# ADE9000_prototipo.net
KiCad netlist of a schematic drawn in EAGLE
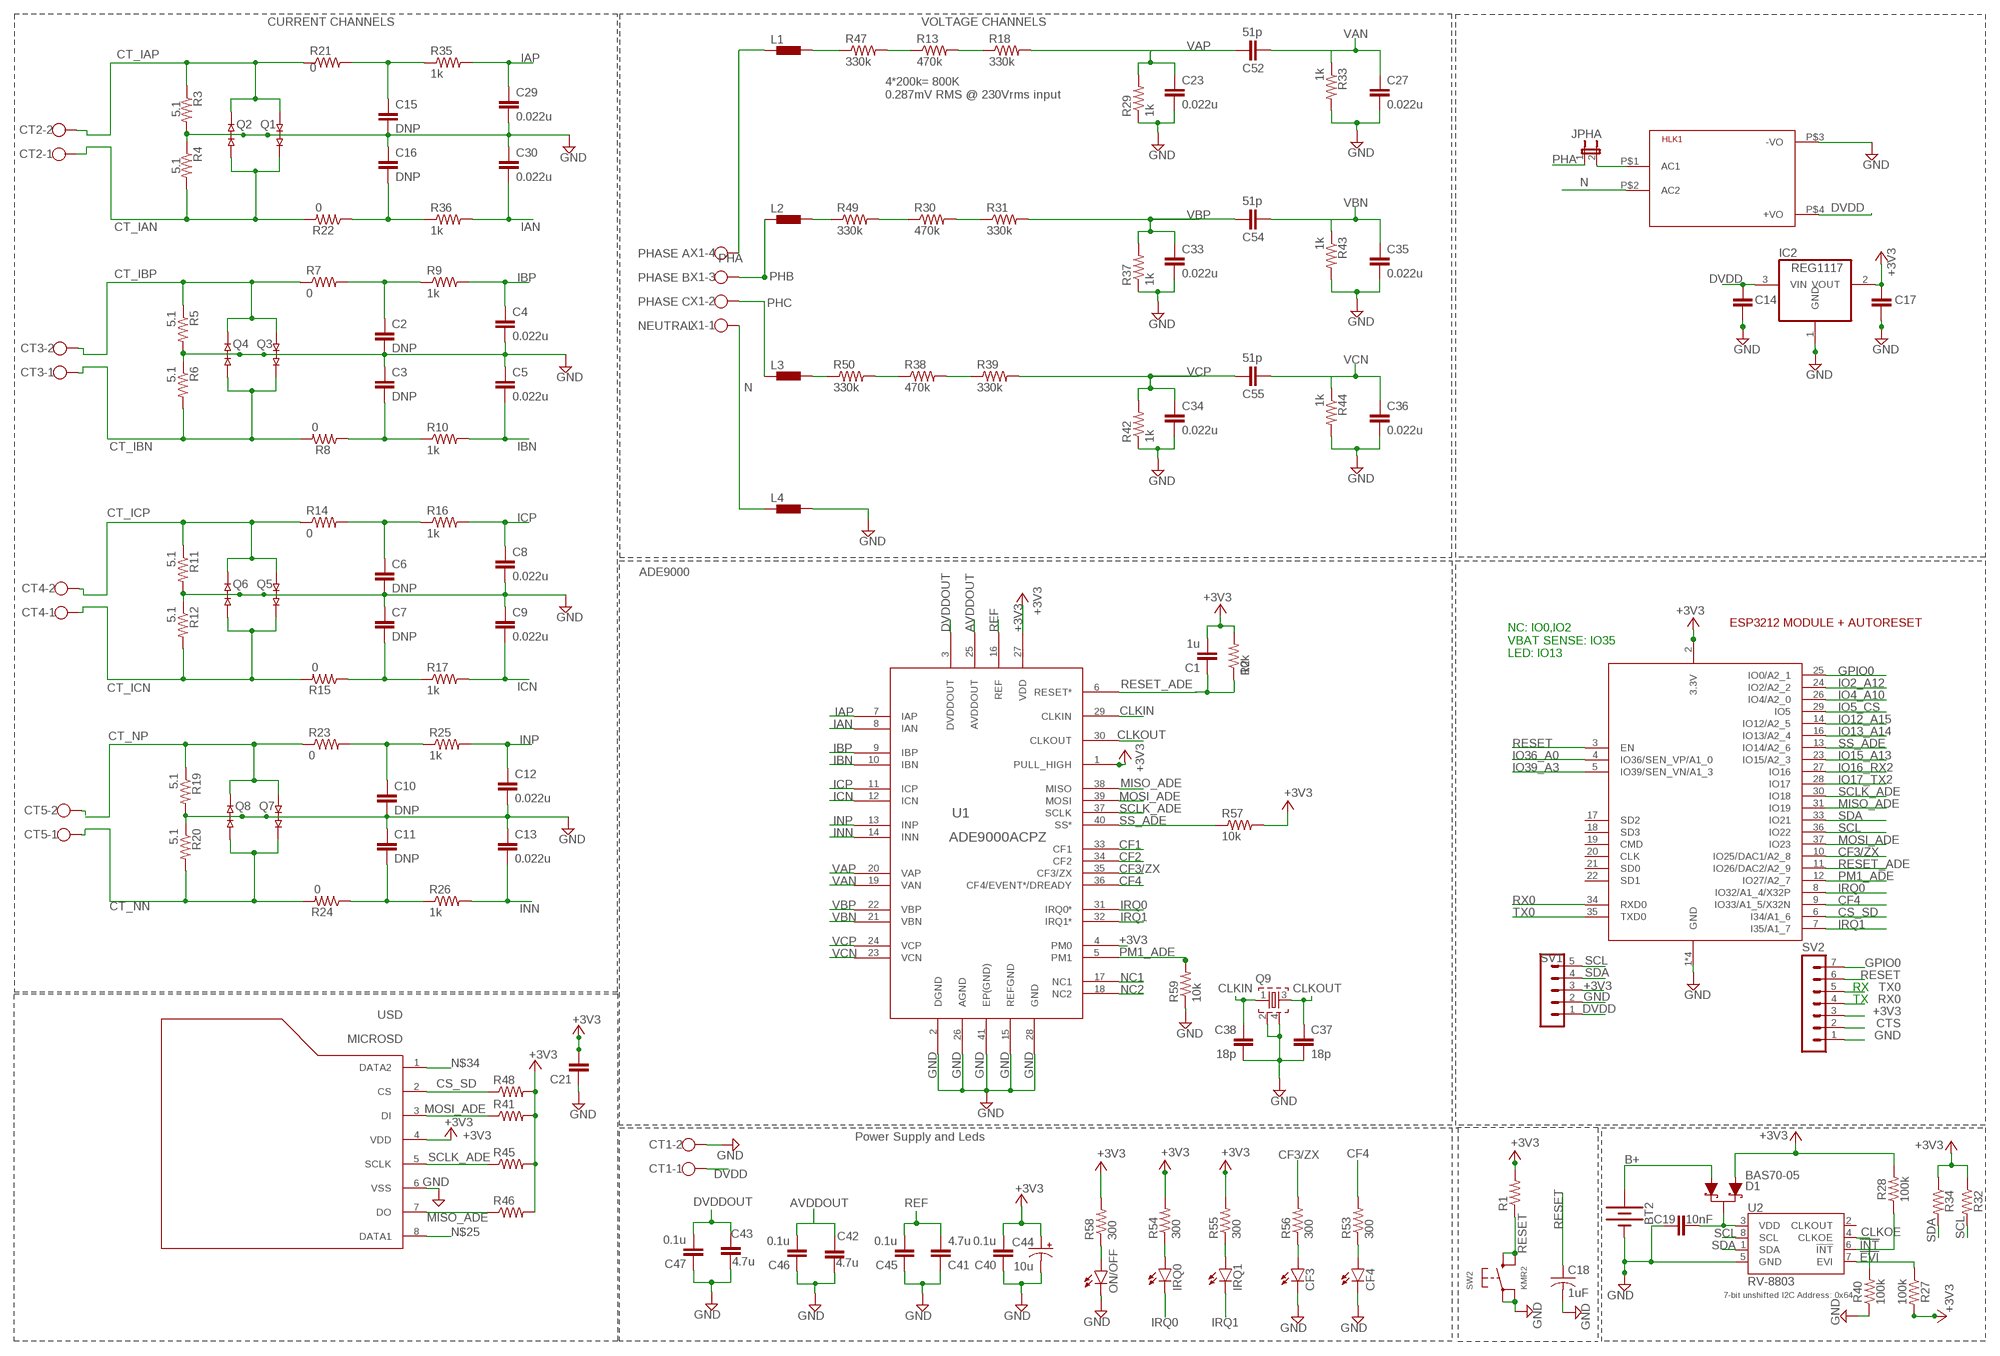
[diagram p0: schematic, sheet 1]

(export (version "E")
  (design (tool "Eeschema 10.0.6"))
  (components
    (comp (ref "BT2")
      (value "BATTERY-12MM_SMD")
      (footprint "eagle-import:BATTCON_12MM")
      (libsource (lib "eagle-import") (part "BATTERY-12MM_SMD"))
    )
    (comp (ref "C1")
      (value "1u")
      (footprint "eagle-import:C0805")
      (libsource (lib "eagle-import") (part "C-EUC0805"))
    )
    (comp (ref "C2")
      (value "DNP")
      (footprint "eagle-import:C0805")
      (libsource (lib "eagle-import") (part "C-EUC0805"))
    )
    (comp (ref "C3")
      (value "DNP")
      (footprint "eagle-import:C0805")
      (libsource (lib "eagle-import") (part "C-EUC0805"))
    )
    (comp (ref "C4")
      (value "0.022u")
      (footprint "eagle-import:C0805")
      (libsource (lib "eagle-import") (part "C-EUC0805"))
    )
    (comp (ref "C5")
      (value "0.022u")
      (footprint "eagle-import:C0805")
      (libsource (lib "eagle-import") (part "C-EUC0805"))
    )
    (comp (ref "C6")
      (value "DNP")
      (footprint "eagle-import:C0805")
      (libsource (lib "eagle-import") (part "C-EUC0805"))
    )
    (comp (ref "C7")
      (value "DNP")
      (footprint "eagle-import:C0805")
      (libsource (lib "eagle-import") (part "C-EUC0805"))
    )
    (comp (ref "C8")
      (value "0.022u")
      (footprint "eagle-import:C0805")
      (libsource (lib "eagle-import") (part "C-EUC0805"))
    )
    (comp (ref "C9")
      (value "0.022u")
      (footprint "eagle-import:C0805")
      (libsource (lib "eagle-import") (part "C-EUC0805"))
    )
    (comp (ref "C10")
      (value "DNP")
      (footprint "eagle-import:C0805")
      (libsource (lib "eagle-import") (part "C-EUC0805"))
    )
    (comp (ref "C11")
      (value "DNP")
      (footprint "eagle-import:C0805")
      (libsource (lib "eagle-import") (part "C-EUC0805"))
    )
    (comp (ref "C12")
      (value "0.022u")
      (footprint "eagle-import:C0805")
      (libsource (lib "eagle-import") (part "C-EUC0805"))
    )
    (comp (ref "C13")
      (value "0.022u")
      (footprint "eagle-import:C0805")
      (libsource (lib "eagle-import") (part "C-EUC0805"))
    )
    (comp (ref "C14")
      (value "C-EUC1206")
      (footprint "eagle-import:C1206")
      (libsource (lib "eagle-import") (part "C-EUC1206"))
    )
    (comp (ref "C15")
      (value "DNP")
      (footprint "eagle-import:C0805")
      (libsource (lib "eagle-import") (part "C-EUC0805"))
    )
    (comp (ref "C16")
      (value "DNP")
      (footprint "eagle-import:C0805")
      (libsource (lib "eagle-import") (part "C-EUC0805"))
    )
    (comp (ref "C17")
      (value "C-EUC1206")
      (footprint "eagle-import:C1206")
      (libsource (lib "eagle-import") (part "C-EUC1206"))
    )
    (comp (ref "C18")
      (value "1uF")
      (footprint "eagle-import:C0805")
      (libsource (lib "eagle-import") (part "C-USC0805"))
    )
    (comp (ref "C19")
      (value "10nF")
      (footprint "eagle-import:0603")
      (libsource (lib "eagle-import") (part "10NF-0603-50V-10%"))
    )
    (comp (ref "C21")
      (value "0.1u")
      (footprint "eagle-import:C0805")
      (libsource (lib "eagle-import") (part "C-EUC0805"))
    )
    (comp (ref "C23")
      (value "0.022u")
      (footprint "eagle-import:C0805")
      (libsource (lib "eagle-import") (part "C-EUC0805"))
    )
    (comp (ref "C27")
      (value "0.022u")
      (footprint "eagle-import:C0603")
      (libsource (lib "eagle-import") (part "C-EUC0603"))
    )
    (comp (ref "C29")
      (value "0.022u")
      (footprint "eagle-import:C0805")
      (libsource (lib "eagle-import") (part "C-EUC0805"))
    )
    (comp (ref "C30")
      (value "0.022u")
      (footprint "eagle-import:C0805")
      (libsource (lib "eagle-import") (part "C-EUC0805"))
    )
    (comp (ref "C33")
      (value "0.022u")
      (footprint "eagle-import:C0805")
      (libsource (lib "eagle-import") (part "C-EUC0805"))
    )
    (comp (ref "C34")
      (value "0.022u")
      (footprint "eagle-import:C0805")
      (libsource (lib "eagle-import") (part "C-EUC0805"))
    )
    (comp (ref "C35")
      (value "0.022u")
      (footprint "eagle-import:C0603")
      (libsource (lib "eagle-import") (part "C-EUC0603"))
    )
    (comp (ref "C36")
      (value "0.022u")
      (footprint "eagle-import:C0603")
      (libsource (lib "eagle-import") (part "C-EUC0603"))
    )
    (comp (ref "C37")
      (value "18p")
      (footprint "eagle-import:C0805")
      (libsource (lib "eagle-import") (part "C-EUC0805"))
    )
    (comp (ref "C38")
      (value "18p")
      (footprint "eagle-import:C0805")
      (libsource (lib "eagle-import") (part "C-EUC0805"))
    )
    (comp (ref "C40")
      (value "0.1u")
      (footprint "eagle-import:C0805")
      (libsource (lib "eagle-import") (part "C-EUC0805"))
    )
    (comp (ref "C41")
      (value "4.7u")
      (footprint "eagle-import:C0805")
      (libsource (lib "eagle-import") (part "C-EUC0805"))
    )
    (comp (ref "C42")
      (value "4.7u")
      (footprint "eagle-import:C0805")
      (libsource (lib "eagle-import") (part "C-EUC0805"))
    )
    (comp (ref "C43")
      (value "4.7u")
      (footprint "eagle-import:C0805")
      (libsource (lib "eagle-import") (part "C-EUC0805"))
    )
    (comp (ref "C44")
      (value "10u")
      (footprint "eagle-import:E1,8-4")
      (libsource (lib "eagle-import") (part "CPOL-USE1.8-4"))
    )
    (comp (ref "C45")
      (value "0.1u")
      (footprint "eagle-import:C0805")
      (libsource (lib "eagle-import") (part "C-EUC0805"))
    )
    (comp (ref "C46")
      (value "0.1u")
      (footprint "eagle-import:C0805")
      (libsource (lib "eagle-import") (part "C-EUC0805"))
    )
    (comp (ref "C47")
      (value "0.1u")
      (footprint "eagle-import:C0805")
      (libsource (lib "eagle-import") (part "C-EUC0805"))
    )
    (comp (ref "C52")
      (value "51p")
      (footprint "eagle-import:C0603")
      (libsource (lib "eagle-import") (part "C-EUC0603"))
    )
    (comp (ref "C54")
      (value "51p")
      (footprint "eagle-import:C0603")
      (libsource (lib "eagle-import") (part "C-EUC0603"))
    )
    (comp (ref "C55")
      (value "51p")
      (footprint "eagle-import:C0603")
      (libsource (lib "eagle-import") (part "C-EUC0603"))
    )
    (comp (ref "CF3")
      (value "LEDCHIPLED_1206")
      (footprint "eagle-import:CHIPLED_1206")
      (libsource (lib "eagle-import") (part "LEDCHIPLED_1206"))
    )
    (comp (ref "CF4")
      (value "LEDCHIPLED_1206")
      (footprint "eagle-import:CHIPLED_1206")
      (libsource (lib "eagle-import") (part "LEDCHIPLED_1206"))
    )
    (comp (ref "CT1")
      (value "W237-102")
      (footprint "eagle-import:W237-102")
      (fields (field (name "MPN") "237-102"))
      (libsource (lib "eagle-import") (part "W237-102"))
    )
    (comp (ref "CT2")
      (value "W237-102")
      (footprint "eagle-import:W237-102")
      (fields (field (name "MPN") "237-102"))
      (libsource (lib "eagle-import") (part "W237-102"))
    )
    (comp (ref "CT3")
      (value "W237-102")
      (footprint "eagle-import:W237-102")
      (fields (field (name "MPN") "237-102"))
      (libsource (lib "eagle-import") (part "W237-102"))
    )
    (comp (ref "CT4")
      (value "W237-102")
      (footprint "eagle-import:W237-102")
      (fields (field (name "MPN") "237-102"))
      (libsource (lib "eagle-import") (part "W237-102"))
    )
    (comp (ref "CT5")
      (value "W237-102")
      (footprint "eagle-import:W237-102")
      (fields (field (name "MPN") "237-102"))
      (libsource (lib "eagle-import") (part "W237-102"))
    )
    (comp (ref "D1")
      (value "BAS70-05")
      (footprint "eagle-import:SOT23-3")
      (libsource (lib "eagle-import") (part "DIODE-SCHOTTKY-DUAL"))
    )
    (comp (ref "HLK1")
      (value "HLK-PM013W")
      (footprint "eagle-import:HLK-PM01")
      (libsource (lib "eagle-import") (part "HLK-PM013W"))
    )
    (comp (ref "IC2")
      (value "REG1117")
      (footprint "eagle-import:SOT223")
      (libsource (lib "eagle-import") (part "REG1117"))
    )
    (comp (ref "IRQ0")
      (value "LEDCHIPLED_1206")
      (footprint "eagle-import:CHIPLED_1206")
      (libsource (lib "eagle-import") (part "LEDCHIPLED_1206"))
    )
    (comp (ref "IRQ1")
      (value "LEDCHIPLED_1206")
      (footprint "eagle-import:CHIPLED_1206")
      (libsource (lib "eagle-import") (part "LEDCHIPLED_1206"))
    )
    (comp (ref "JPHA")
      (value "JP1E")
      (footprint "eagle-import:JP1")
      (libsource (lib "eagle-import") (part "JP1E"))
    )
    (comp (ref "L1")
      (value "1500")
      (footprint "eagle-import:M0805")
      (libsource (lib "eagle-import") (part "FERRITE_BEAD0805"))
    )
    (comp (ref "L2")
      (value "1500")
      (footprint "eagle-import:M0805")
      (libsource (lib "eagle-import") (part "FERRITE_BEAD0805"))
    )
    (comp (ref "L3")
      (value "1500")
      (footprint "eagle-import:M0805")
      (libsource (lib "eagle-import") (part "FERRITE_BEAD0805"))
    )
    (comp (ref "L4")
      (value "1500")
      (footprint "eagle-import:M0805")
      (libsource (lib "eagle-import") (part "FERRITE_BEAD0805"))
    )
    (comp (ref "ON/OFF")
      (value "LEDCHIPLED_1206")
      (footprint "eagle-import:CHIPLED_1206")
      (libsource (lib "eagle-import") (part "LEDCHIPLED_1206"))
    )
    (comp (ref "Q1")
      (value "MMBD4148SE")
      (footprint "eagle-import:SOT23-3")
      (libsource (lib "eagle-import") (part "DUAL_DIODE_SOT23-3"))
    )
    (comp (ref "Q2")
      (value "MMBD4148SE")
      (footprint "eagle-import:SOT23-3")
      (libsource (lib "eagle-import") (part "DUAL_DIODE_SOT23-3"))
    )
    (comp (ref "Q3")
      (value "MMBD4148SE")
      (footprint "eagle-import:SOT23-3")
      (libsource (lib "eagle-import") (part "DUAL_DIODE_SOT23-3"))
    )
    (comp (ref "Q4")
      (value "MMBD4148SE")
      (footprint "eagle-import:SOT23-3")
      (libsource (lib "eagle-import") (part "DUAL_DIODE_SOT23-3"))
    )
    (comp (ref "Q5")
      (value "MMBD4148SE")
      (footprint "eagle-import:SOT23-3")
      (libsource (lib "eagle-import") (part "DUAL_DIODE_SOT23-3"))
    )
    (comp (ref "Q6")
      (value "MMBD4148SE")
      (footprint "eagle-import:SOT23-3")
      (libsource (lib "eagle-import") (part "DUAL_DIODE_SOT23-3"))
    )
    (comp (ref "Q7")
      (value "MMBD4148SE")
      (footprint "eagle-import:SOT23-3")
      (libsource (lib "eagle-import") (part "DUAL_DIODE_SOT23-3"))
    )
    (comp (ref "Q8")
      (value "MMBD4148SE")
      (footprint "eagle-import:SOT23-3")
      (libsource (lib "eagle-import") (part "DUAL_DIODE_SOT23-3"))
    )
    (comp (ref "Q9")
      (value "ECS-245.7-12-33Q-JES-TR")
      (footprint "eagle-import:SMD_4PIN_3.2X2.1")
      (libsource (lib "eagle-import") (part "CRYSTAL_SMD128"))
    )
    (comp (ref "R1")
      (value "R-US_R0805")
      (footprint "eagle-import:R0805")
      (libsource (lib "eagle-import") (part "R-US_R0805"))
    )
    (comp (ref "R2")
      (value "10k")
      (footprint "eagle-import:R0805")
      (libsource (lib "eagle-import") (part "R-US_R0805"))
    )
    (comp (ref "R3")
      (value "5.1")
      (footprint "eagle-import:R0805")
      (description "RES, 5.1, 0W1, 0%1, 0805-SMT, ROHS")
      (fields (field (name "MANUFACTURER") " TE Connectivity Passive Product"))
      (libsource (lib "eagle-import") (part "R-US_R0805"))
    )
    (comp (ref "R4")
      (value "5.1")
      (footprint "eagle-import:R0805")
      (libsource (lib "eagle-import") (part "R-US_R0805"))
    )
    (comp (ref "R5")
      (value "5.1")
      (footprint "eagle-import:R0805")
      (description "RES, 5.1, 0W1, 0%1, 0805-SMT, ROHS")
      (fields (field (name "MANUFACTURER") " TE Connectivity Passive Product"))
      (libsource (lib "eagle-import") (part "R-US_R0805"))
    )
    (comp (ref "R6")
      (value "5.1")
      (footprint "eagle-import:R0805")
      (libsource (lib "eagle-import") (part "R-US_R0805"))
    )
    (comp (ref "R7")
      (value "0")
      (footprint "eagle-import:R0805")
      (libsource (lib "eagle-import") (part "R-US_R0805"))
    )
    (comp (ref "R8")
      (value "0")
      (footprint "eagle-import:R0805")
      (libsource (lib "eagle-import") (part "R-US_R0805"))
    )
    (comp (ref "R9")
      (value "1k")
      (footprint "eagle-import:R0805")
      (libsource (lib "eagle-import") (part "R-US_R0805"))
    )
    (comp (ref "R10")
      (value "1k")
      (footprint "eagle-import:R0805")
      (libsource (lib "eagle-import") (part "R-US_R0805"))
    )
    (comp (ref "R11")
      (value "5.1")
      (footprint "eagle-import:R0805")
      (description "RES, 5.1, 0W1, 0%1, 0805-SMT, ROHS")
      (fields (field (name "MANUFACTURER") " TE Connectivity Passive Product"))
      (libsource (lib "eagle-import") (part "R-US_R0805"))
    )
    (comp (ref "R12")
      (value "5.1")
      (footprint "eagle-import:R0805")
      (libsource (lib "eagle-import") (part "R-US_R0805"))
    )
    (comp (ref "R13")
      (value "470k")
      (footprint "eagle-import:R0805")
      (libsource (lib "eagle-import") (part "R-US_R0805"))
    )
    (comp (ref "R14")
      (value "0")
      (footprint "eagle-import:R0805")
      (libsource (lib "eagle-import") (part "R-US_R0805"))
    )
    (comp (ref "R15")
      (value "0")
      (footprint "eagle-import:R0805")
      (libsource (lib "eagle-import") (part "R-US_R0805"))
    )
    (comp (ref "R16")
      (value "1k")
      (footprint "eagle-import:R0805")
      (libsource (lib "eagle-import") (part "R-US_R0805"))
    )
    (comp (ref "R17")
      (value "1k")
      (footprint "eagle-import:R0805")
      (libsource (lib "eagle-import") (part "R-US_R0805"))
    )
    (comp (ref "R18")
      (value "330k")
      (footprint "eagle-import:R0805")
      (libsource (lib "eagle-import") (part "R-US_R0805"))
    )
    (comp (ref "R19")
      (value "5.1")
      (footprint "eagle-import:R0805")
      (description "RES, 5.1, 0W1, 0%1, 0805-SMT, ROHS")
      (fields (field (name "MANUFACTURER") " TE Connectivity Passive Product"))
      (libsource (lib "eagle-import") (part "R-US_R0805"))
    )
    (comp (ref "R20")
      (value "5.1")
      (footprint "eagle-import:R0805")
      (libsource (lib "eagle-import") (part "R-US_R0805"))
    )
    (comp (ref "R21")
      (value "0")
      (footprint "eagle-import:R0805")
      (libsource (lib "eagle-import") (part "R-US_R0805"))
    )
    (comp (ref "R22")
      (value "0")
      (footprint "eagle-import:R0805")
      (libsource (lib "eagle-import") (part "R-US_R0805"))
    )
    (comp (ref "R23")
      (value "0")
      (footprint "eagle-import:R0805")
      (libsource (lib "eagle-import") (part "R-US_R0805"))
    )
    (comp (ref "R24")
      (value "0")
      (footprint "eagle-import:R0805")
      (libsource (lib "eagle-import") (part "R-US_R0805"))
    )
    (comp (ref "R25")
      (value "1k")
      (footprint "eagle-import:R0805")
      (libsource (lib "eagle-import") (part "R-US_R0805"))
    )
    (comp (ref "R26")
      (value "1k")
      (footprint "eagle-import:R0805")
      (libsource (lib "eagle-import") (part "R-US_R0805"))
    )
    (comp (ref "R27")
      (value "100k")
      (footprint "eagle-import:0603")
      (libsource (lib "eagle-import") (part "100KOHM-0603-1/10W-1%"))
    )
    (comp (ref "R28")
      (value "100k")
      (footprint "eagle-import:0603")
      (libsource (lib "eagle-import") (part "100KOHM-0603-1/10W-1%"))
    )
    (comp (ref "R29")
      (value "1k")
      (footprint "eagle-import:R0805")
      (libsource (lib "eagle-import") (part "R-US_R0805"))
    )
    (comp (ref "R30")
      (value "470k")
      (footprint "eagle-import:R0805")
      (libsource (lib "eagle-import") (part "R-US_R0805"))
    )
    (comp (ref "R31")
      (value "330k")
      (footprint "eagle-import:R0805")
      (libsource (lib "eagle-import") (part "R-US_R0805"))
    )
    (comp (ref "R32")
      (value "4.7k")
      (footprint "eagle-import:0603")
      (libsource (lib "eagle-import") (part "4.7KOHM-0603-1/10W-1%"))
    )
    (comp (ref "R33")
      (value "1k")
      (footprint "eagle-import:R0603")
      (libsource (lib "eagle-import") (part "R-US_R0603"))
    )
    (comp (ref "R34")
      (value "4.7KOHM-0603-1/10W-1%")
      (footprint "eagle-import:0603")
      (libsource (lib "eagle-import") (part "4.7KOHM-0603-1/10W-1%"))
    )
    (comp (ref "R35")
      (value "1k")
      (footprint "eagle-import:R0805")
      (libsource (lib "eagle-import") (part "R-US_R0805"))
    )
    (comp (ref "R36")
      (value "1k")
      (footprint "eagle-import:R0805")
      (libsource (lib "eagle-import") (part "R-US_R0805"))
    )
    (comp (ref "R37")
      (value "1k")
      (footprint "eagle-import:R0805")
      (libsource (lib "eagle-import") (part "R-US_R0805"))
    )
    (comp (ref "R38")
      (value "470k")
      (footprint "eagle-import:R0805")
      (libsource (lib "eagle-import") (part "R-US_R0805"))
    )
    (comp (ref "R39")
      (value "330k")
      (footprint "eagle-import:R0805")
      (libsource (lib "eagle-import") (part "R-US_R0805"))
    )
    (comp (ref "R40")
      (value "100k")
      (footprint "eagle-import:0603")
      (libsource (lib "eagle-import") (part "100KOHM-0603-1/10W-1%"))
    )
    (comp (ref "R41")
      (value "R-US_R0805")
      (footprint "eagle-import:R0805")
      (libsource (lib "eagle-import") (part "R-US_R0805"))
    )
    (comp (ref "R42")
      (value "1k")
      (footprint "eagle-import:R0805")
      (libsource (lib "eagle-import") (part "R-US_R0805"))
    )
    (comp (ref "R43")
      (value "1k")
      (footprint "eagle-import:R0603")
      (libsource (lib "eagle-import") (part "R-US_R0603"))
    )
    (comp (ref "R44")
      (value "1k")
      (footprint "eagle-import:R0603")
      (libsource (lib "eagle-import") (part "R-US_R0603"))
    )
    (comp (ref "R45")
      (value "R-US_R0805")
      (footprint "eagle-import:R0805")
      (libsource (lib "eagle-import") (part "R-US_R0805"))
    )
    (comp (ref "R46")
      (value "R-US_R0805")
      (footprint "eagle-import:R0805")
      (libsource (lib "eagle-import") (part "R-US_R0805"))
    )
    (comp (ref "R47")
      (value "330k")
      (footprint "eagle-import:R0805")
      (libsource (lib "eagle-import") (part "R-US_R0805"))
    )
    (comp (ref "R48")
      (value "R-US_R0805")
      (footprint "eagle-import:R0805")
      (libsource (lib "eagle-import") (part "R-US_R0805"))
    )
    (comp (ref "R49")
      (value "330k")
      (footprint "eagle-import:R0805")
      (libsource (lib "eagle-import") (part "R-US_R0805"))
    )
    (comp (ref "R50")
      (value "330k")
      (footprint "eagle-import:R0805")
      (libsource (lib "eagle-import") (part "R-US_R0805"))
    )
    (comp (ref "R53")
      (value "300")
      (footprint "eagle-import:R0805")
      (libsource (lib "eagle-import") (part "R-US_R0805"))
    )
    (comp (ref "R54")
      (value "300")
      (footprint "eagle-import:R0805")
      (libsource (lib "eagle-import") (part "R-US_R0805"))
    )
    (comp (ref "R55")
      (value "300")
      (footprint "eagle-import:R0805")
      (libsource (lib "eagle-import") (part "R-US_R0805"))
    )
    (comp (ref "R56")
      (value "300")
      (footprint "eagle-import:R0805")
      (libsource (lib "eagle-import") (part "R-US_R0805"))
    )
    (comp (ref "R57")
      (value "10k")
      (footprint "eagle-import:R0805")
      (libsource (lib "eagle-import") (part "R-US_R0805"))
    )
    (comp (ref "R58")
      (value "300")
      (footprint "eagle-import:R0805")
      (libsource (lib "eagle-import") (part "R-US_R0805"))
    )
    (comp (ref "R59")
      (value "10k")
      (footprint "eagle-import:R0805")
      (libsource (lib "eagle-import") (part "R-US_R0805"))
    )
    (comp (ref "SV1")
      (value "MA05-1")
      (footprint "eagle-import:MA05-1")
      (libsource (lib "eagle-import") (part "MA05-1"))
    )
    (comp (ref "SV2")
      (value "MA07-1")
      (footprint "eagle-import:MA07-1")
      (libsource (lib "eagle-import") (part "MA07-1"))
    )
    (comp (ref "SW2")
      (value "KMR2")
      (footprint "eagle-import:BTN_KMR2_4.6X2.8")
      (libsource (lib "eagle-import") (part "SWITCH_TACT_SMT4.6X2.8"))
    )
    (comp (ref "U1")
      (value "ADE9000ACPZ")
      (footprint "eagle-import:CP_40_7")
      (libsource (lib "eagle-import") (part "ADE9000ACPZ"))
    )
    (comp (ref "U2")
      (value "RV-8803")
      (footprint "eagle-import:RV-3028")
      (libsource (lib "eagle-import") (part "RV-8803"))
    )
    (comp (ref "USD")
      (value "MICROSD")
      (footprint "eagle-import:MICROSD")
      (libsource (lib "eagle-import") (part "MICROSD"))
    )
    (comp (ref "X1")
      (value "W237-4")
      (footprint "eagle-import:W237-4")
      (libsource (lib "eagle-import") (part "W237-4"))
    )
    (comp (ref "X4")
      (value "ESP32_WROOM32_SKINNY")
      (footprint "eagle-import:WROOM32_SKINNY")
      (libsource (lib "eagle-import") (part "ESP32_WROOM32_SKINNY"))
    )
  )
  (nets
    (net (code "1") (name "+3V3") (class "Default")
      (node (ref "C1") (pin "2") (pinfunction "2_2") (pintype "passive"))
      (node (ref "C17") (pin "1") (pinfunction "1_1") (pintype "passive"))
      (node (ref "C21") (pin "2") (pinfunction "2_2") (pintype "passive"))
      (node (ref "C40") (pin "2") (pinfunction "2_2") (pintype "passive"))
      (node (ref "C44") (pin "+") (pinfunction "+_+") (pintype "passive"))
      (node (ref "D1") (pin "1") (pinfunction "A_1") (pintype "passive"))
      (node (ref "IC2") (pin "2") (pinfunction "VOUT_2") (pintype "output"))
      (node (ref "R1") (pin "2") (pinfunction "2_2") (pintype "passive"))
      (node (ref "R2") (pin "2") (pinfunction "2_2") (pintype "passive"))
      (node (ref "R27") (pin "2") (pinfunction "2_2") (pintype "passive"))
      (node (ref "R28") (pin "2") (pinfunction "2_2") (pintype "passive"))
      (node (ref "R32") (pin "1") (pinfunction "1_1") (pintype "passive"))
      (node (ref "R34") (pin "1") (pinfunction "1_1") (pintype "passive"))
      (node (ref "R41") (pin "2") (pinfunction "2_2") (pintype "passive"))
      (node (ref "R45") (pin "2") (pinfunction "2_2") (pintype "passive"))
      (node (ref "R46") (pin "2") (pinfunction "2_2") (pintype "passive"))
      (node (ref "R48") (pin "2") (pinfunction "2_2") (pintype "passive"))
      (node (ref "R54") (pin "2") (pinfunction "2_2") (pintype "passive"))
      (node (ref "R55") (pin "2") (pinfunction "2_2") (pintype "passive"))
      (node (ref "R57") (pin "2") (pinfunction "2_2") (pintype "passive"))
      (node (ref "R58") (pin "2") (pinfunction "2_2") (pintype "passive"))
      (node (ref "SV1") (pin "3") (pinfunction "3_3") (pintype "passive"))
      (node (ref "SV2") (pin "3") (pinfunction "3_3") (pintype "passive"))
      (node (ref "U1") (pin "1") (pinfunction "PULL_HIGH_1") (pintype "passive"))
      (node (ref "U1") (pin "27") (pinfunction "VDD_27") (pintype "passive"))
      (node (ref "U1") (pin "4") (pinfunction "PM0_4") (pintype "passive"))
      (node (ref "USD") (pin "4") (pinfunction "VDD_4") (pintype "bidirectional"))
      (node (ref "X4") (pin "2") (pinfunction "3.3V_2") (pintype "passive"))
    )
    (net (code "2") (name "/AVDDOUT") (class "Default")
      (node (ref "C42") (pin "1") (pinfunction "1_1") (pintype "passive"))
      (node (ref "C46") (pin "2") (pinfunction "2_2") (pintype "passive"))
      (node (ref "U1") (pin "25") (pinfunction "AVDDOUT_25") (pintype "passive"))
    )
    (net (code "3") (name "/B+") (class "Default")
      (node (ref "BT2") (pin "PWR@1") (pinfunction "+_PWR@1") (pintype "power_in"))
      (node (ref "D1") (pin "2") (pinfunction "A1_2") (pintype "passive"))
    )
    (net (code "4") (name "/CF1") (class "Default")
      (node (ref "U1") (pin "33") (pinfunction "CF1_33") (pintype "passive"))
    )
    (net (code "5") (name "/CF2") (class "Default")
      (node (ref "U1") (pin "34") (pinfunction "CF2_34") (pintype "passive"))
    )
    (net (code "6") (name "/CF3{slash}ZX") (class "Default")
      (node (ref "R56") (pin "2") (pinfunction "2_2") (pintype "passive"))
      (node (ref "U1") (pin "35") (pinfunction "CF3/ZX_35") (pintype "passive"))
      (node (ref "X4") (pin "10") (pinfunction "IO25/DAC1/A2_8_10") (pintype "bidirectional"))
    )
    (net (code "7") (name "/CF4") (class "Default")
      (node (ref "R53") (pin "2") (pinfunction "2_2") (pintype "passive"))
      (node (ref "U1") (pin "36") (pinfunction "CF4/EVENT*/DREADY_36") (pintype "passive"))
      (node (ref "X4") (pin "9") (pinfunction "IO33/A1_5/X32N_9") (pintype "bidirectional"))
    )
    (net (code "8") (name "/CLKIN") (class "Default")
      (node (ref "C38") (pin "1") (pinfunction "1_1") (pintype "passive"))
      (node (ref "Q9") (pin "1") (pinfunction "1_1") (pintype "passive"))
      (node (ref "U1") (pin "29") (pinfunction "CLKIN_29") (pintype "passive"))
    )
    (net (code "9") (name "/CLKOE") (class "Default")
      (node (ref "R40") (pin "2") (pinfunction "2_2") (pintype "passive"))
      (node (ref "U2") (pin "4") (pinfunction "CLKOE_4") (pintype "bidirectional"))
    )
    (net (code "10") (name "/CLKOUT") (class "Default")
      (node (ref "C37") (pin "1") (pinfunction "1_1") (pintype "passive"))
      (node (ref "Q9") (pin "3") (pinfunction "3_3") (pintype "passive"))
      (node (ref "U1") (pin "30") (pinfunction "CLKOUT_30") (pintype "passive"))
    )
    (net (code "11") (name "/CS_SD") (class "Default")
      (node (ref "R48") (pin "1") (pinfunction "1_1") (pintype "passive"))
      (node (ref "USD") (pin "2") (pinfunction "CS_2") (pintype "bidirectional"))
      (node (ref "X4") (pin "6") (pinfunction "I34/A1_6_6") (pintype "bidirectional"))
    )
    (net (code "12") (name "/CTS") (class "Default")
      (node (ref "SV2") (pin "2") (pinfunction "2_2") (pintype "passive"))
    )
    (net (code "13") (name "/CT_IAN") (class "Default")
      (node (ref "CT2") (pin "1") (pinfunction "KL_1") (pintype "passive"))
      (node (ref "Q1") (pin "2") (pinfunction "2_2") (pintype "passive"))
      (node (ref "Q2") (pin "1") (pinfunction "1_1") (pintype "passive"))
      (node (ref "R22") (pin "2") (pinfunction "2_2") (pintype "passive"))
      (node (ref "R4") (pin "2") (pinfunction "2_2") (pintype "passive"))
    )
    (net (code "14") (name "/CT_IAP") (class "Default")
      (node (ref "CT2") (pin "2") (pinfunction "KL_2") (pintype "passive"))
      (node (ref "Q1") (pin "1") (pinfunction "1_1") (pintype "passive"))
      (node (ref "Q2") (pin "2") (pinfunction "2_2") (pintype "passive"))
      (node (ref "R21") (pin "1") (pinfunction "1_1") (pintype "passive"))
      (node (ref "R3") (pin "1") (pinfunction "1_1") (pintype "passive"))
    )
    (net (code "15") (name "/CT_IBN") (class "Default")
      (node (ref "CT3") (pin "1") (pinfunction "KL_1") (pintype "passive"))
      (node (ref "Q3") (pin "2") (pinfunction "2_2") (pintype "passive"))
      (node (ref "Q4") (pin "1") (pinfunction "1_1") (pintype "passive"))
      (node (ref "R6") (pin "2") (pinfunction "2_2") (pintype "passive"))
      (node (ref "R8") (pin "2") (pinfunction "2_2") (pintype "passive"))
    )
    (net (code "16") (name "/CT_IBP") (class "Default")
      (node (ref "CT3") (pin "2") (pinfunction "KL_2") (pintype "passive"))
      (node (ref "Q3") (pin "1") (pinfunction "1_1") (pintype "passive"))
      (node (ref "Q4") (pin "2") (pinfunction "2_2") (pintype "passive"))
      (node (ref "R5") (pin "1") (pinfunction "1_1") (pintype "passive"))
      (node (ref "R7") (pin "1") (pinfunction "1_1") (pintype "passive"))
    )
    (net (code "17") (name "/CT_ICN") (class "Default")
      (node (ref "CT4") (pin "1") (pinfunction "KL_1") (pintype "passive"))
      (node (ref "Q5") (pin "2") (pinfunction "2_2") (pintype "passive"))
      (node (ref "Q6") (pin "1") (pinfunction "1_1") (pintype "passive"))
      (node (ref "R12") (pin "2") (pinfunction "2_2") (pintype "passive"))
      (node (ref "R15") (pin "2") (pinfunction "2_2") (pintype "passive"))
    )
    (net (code "18") (name "/CT_ICP") (class "Default")
      (node (ref "CT4") (pin "2") (pinfunction "KL_2") (pintype "passive"))
      (node (ref "Q5") (pin "1") (pinfunction "1_1") (pintype "passive"))
      (node (ref "Q6") (pin "2") (pinfunction "2_2") (pintype "passive"))
      (node (ref "R11") (pin "1") (pinfunction "1_1") (pintype "passive"))
      (node (ref "R14") (pin "1") (pinfunction "1_1") (pintype "passive"))
    )
    (net (code "19") (name "/CT_NN") (class "Default")
      (node (ref "CT5") (pin "1") (pinfunction "KL_1") (pintype "passive"))
      (node (ref "Q7") (pin "2") (pinfunction "2_2") (pintype "passive"))
      (node (ref "Q8") (pin "1") (pinfunction "1_1") (pintype "passive"))
      (node (ref "R20") (pin "2") (pinfunction "2_2") (pintype "passive"))
      (node (ref "R24") (pin "2") (pinfunction "2_2") (pintype "passive"))
    )
    (net (code "20") (name "/CT_NP") (class "Default")
      (node (ref "CT5") (pin "2") (pinfunction "KL_2") (pintype "passive"))
      (node (ref "Q7") (pin "1") (pinfunction "1_1") (pintype "passive"))
      (node (ref "Q8") (pin "2") (pinfunction "2_2") (pintype "passive"))
      (node (ref "R19") (pin "1") (pinfunction "1_1") (pintype "passive"))
      (node (ref "R23") (pin "1") (pinfunction "1_1") (pintype "passive"))
    )
    (net (code "21") (name "/DVDD") (class "Default")
      (node (ref "C14") (pin "1") (pinfunction "1_1") (pintype "passive"))
      (node (ref "CT1") (pin "1") (pinfunction "KL_1") (pintype "passive"))
      (node (ref "HLK1") (pin "P$4") (pinfunction "+VO_P$4") (pintype "bidirectional"))
      (node (ref "IC2") (pin "3") (pinfunction "VIN_3") (pintype "input"))
      (node (ref "SV1") (pin "1") (pinfunction "1_1") (pintype "passive"))
    )
    (net (code "22") (name "/DVDDOUT") (class "Default")
      (node (ref "C43") (pin "1") (pinfunction "1_1") (pintype "passive"))
      (node (ref "C47") (pin "2") (pinfunction "2_2") (pintype "passive"))
      (node (ref "U1") (pin "3") (pinfunction "DVDDOUT_3") (pintype "passive"))
    )
    (net (code "23") (name "/GPIO0") (class "Default")
      (node (ref "SV2") (pin "7") (pinfunction "7_7") (pintype "passive"))
      (node (ref "X4") (pin "25") (pinfunction "IO0/A2_1_25") (pintype "bidirectional"))
    )
    (net (code "24") (name "/IAN") (class "Default")
      (node (ref "C30") (pin "2") (pinfunction "2_2") (pintype "passive"))
      (node (ref "R36") (pin "2") (pinfunction "2_2") (pintype "passive"))
      (node (ref "U1") (pin "8") (pinfunction "IAN_8") (pintype "passive"))
    )
    (net (code "25") (name "/IAP") (class "Default")
      (node (ref "C29") (pin "1") (pinfunction "1_1") (pintype "passive"))
      (node (ref "R35") (pin "2") (pinfunction "2_2") (pintype "passive"))
      (node (ref "U1") (pin "7") (pinfunction "IAP_7") (pintype "passive"))
    )
    (net (code "26") (name "/IBN") (class "Default")
      (node (ref "C5") (pin "2") (pinfunction "2_2") (pintype "passive"))
      (node (ref "R10") (pin "2") (pinfunction "2_2") (pintype "passive"))
      (node (ref "U1") (pin "10") (pinfunction "IBN_10") (pintype "passive"))
    )
    (net (code "27") (name "/IBP") (class "Default")
      (node (ref "C4") (pin "1") (pinfunction "1_1") (pintype "passive"))
      (node (ref "R9") (pin "2") (pinfunction "2_2") (pintype "passive"))
      (node (ref "U1") (pin "9") (pinfunction "IBP_9") (pintype "passive"))
    )
    (net (code "28") (name "/ICN") (class "Default")
      (node (ref "C9") (pin "2") (pinfunction "2_2") (pintype "passive"))
      (node (ref "R17") (pin "2") (pinfunction "2_2") (pintype "passive"))
      (node (ref "U1") (pin "12") (pinfunction "ICN_12") (pintype "passive"))
    )
    (net (code "29") (name "/ICP") (class "Default")
      (node (ref "C8") (pin "1") (pinfunction "1_1") (pintype "passive"))
      (node (ref "R16") (pin "2") (pinfunction "2_2") (pintype "passive"))
      (node (ref "U1") (pin "11") (pinfunction "ICP_11") (pintype "passive"))
    )
    (net (code "30") (name "/INN") (class "Default")
      (node (ref "C13") (pin "2") (pinfunction "2_2") (pintype "passive"))
      (node (ref "R26") (pin "2") (pinfunction "2_2") (pintype "passive"))
      (node (ref "U1") (pin "14") (pinfunction "INN_14") (pintype "passive"))
    )
    (net (code "31") (name "/INP") (class "Default")
      (node (ref "C12") (pin "1") (pinfunction "1_1") (pintype "passive"))
      (node (ref "R25") (pin "2") (pinfunction "2_2") (pintype "passive"))
      (node (ref "U1") (pin "13") (pinfunction "INP_13") (pintype "passive"))
    )
    (net (code "32") (name "/IO2_A12") (class "Default")
      (node (ref "X4") (pin "24") (pinfunction "IO2/A2_2_24") (pintype "bidirectional"))
    )
    (net (code "33") (name "/IO4_A10") (class "Default")
      (node (ref "X4") (pin "26") (pinfunction "IO4/A2_0_26") (pintype "bidirectional"))
    )
    (net (code "34") (name "/IO5_CS") (class "Default")
      (node (ref "X4") (pin "29") (pinfunction "IO5_29") (pintype "bidirectional"))
    )
    (net (code "35") (name "/IO12_A15") (class "Default")
      (node (ref "X4") (pin "14") (pinfunction "IO12/A2_5_14") (pintype "bidirectional"))
    )
    (net (code "36") (name "/IO13_A14") (class "Default")
      (node (ref "X4") (pin "16") (pinfunction "IO13/A2_4_16") (pintype "bidirectional"))
    )
    (net (code "37") (name "/IO15_A13") (class "Default")
      (node (ref "X4") (pin "23") (pinfunction "IO15/A2_3_23") (pintype "bidirectional"))
    )
    (net (code "38") (name "/IO16_RX2") (class "Default")
      (node (ref "X4") (pin "27") (pinfunction "IO16_27") (pintype "bidirectional"))
    )
    (net (code "39") (name "/IO17_TX2") (class "Default")
      (node (ref "X4") (pin "28") (pinfunction "IO17_28") (pintype "bidirectional"))
    )
    (net (code "40") (name "/IO36_A0") (class "Default")
      (node (ref "X4") (pin "4") (pinfunction "IO36/SEN_VP/A1_0_4") (pintype "passive"))
    )
    (net (code "41") (name "/IO39_A3") (class "Default")
      (node (ref "X4") (pin "5") (pinfunction "IO39/SEN_VN/A1_3_5") (pintype "passive"))
    )
    (net (code "42") (name "/IRQ0") (class "Default")
      (node (ref "IRQ0") (pin "C") (pinfunction "C_C") (pintype "passive"))
      (node (ref "U1") (pin "31") (pinfunction "IRQ0*_31") (pintype "passive"))
      (node (ref "X4") (pin "8") (pinfunction "IO32/A1_4/X32P_8") (pintype "bidirectional"))
    )
    (net (code "43") (name "/IRQ1") (class "Default")
      (node (ref "IRQ1") (pin "C") (pinfunction "C_C") (pintype "passive"))
      (node (ref "U1") (pin "32") (pinfunction "IRQ1*_32") (pintype "passive"))
      (node (ref "X4") (pin "7") (pinfunction "I35/A1_7_7") (pintype "bidirectional"))
    )
    (net (code "44") (name "/MISO_ADE") (class "Default")
      (node (ref "R46") (pin "1") (pinfunction "1_1") (pintype "passive"))
      (node (ref "U1") (pin "38") (pinfunction "MISO_38") (pintype "passive"))
      (node (ref "USD") (pin "7") (pinfunction "DO_7") (pintype "bidirectional"))
      (node (ref "X4") (pin "31") (pinfunction "IO19_31") (pintype "bidirectional"))
    )
    (net (code "45") (name "/MOSI_ADE") (class "Default")
      (node (ref "R41") (pin "1") (pinfunction "1_1") (pintype "passive"))
      (node (ref "U1") (pin "39") (pinfunction "MOSI_39") (pintype "passive"))
      (node (ref "USD") (pin "3") (pinfunction "DI_3") (pintype "bidirectional"))
      (node (ref "X4") (pin "37") (pinfunction "IO23_37") (pintype "bidirectional"))
    )
    (net (code "46") (name "/N") (class "Default")
      (node (ref "HLK1") (pin "P$2") (pinfunction "AC2_P$2") (pintype "bidirectional"))
      (node (ref "L4") (pin "1") (pinfunction "1_1") (pintype "passive"))
      (node (ref "X1") (pin "1") (pinfunction "KL_1") (pintype "passive"))
    )
    (net (code "47") (name "/N$25") (class "Default")
      (node (ref "USD") (pin "8") (pinfunction "DATA1_8") (pintype "bidirectional"))
    )
    (net (code "48") (name "/N$34") (class "Default")
      (node (ref "USD") (pin "1") (pinfunction "DATA2_1") (pintype "bidirectional"))
    )
    (net (code "49") (name "/NC1") (class "Default")
      (node (ref "U1") (pin "17") (pinfunction "NC1_17") (pintype "passive"))
    )
    (net (code "50") (name "/NC2") (class "Default")
      (node (ref "U1") (pin "18") (pinfunction "NC2_18") (pintype "passive"))
    )
    (net (code "51") (name "/PHA") (class "Default")
      (node (ref "JPHA") (pin "1") (pinfunction "1_1") (pintype "passive"))
      (node (ref "L1") (pin "1") (pinfunction "1_1") (pintype "passive"))
      (node (ref "X1") (pin "4") (pinfunction "KL_4") (pintype "passive"))
    )
    (net (code "52") (name "/PHB") (class "Default")
      (node (ref "L2") (pin "1") (pinfunction "1_1") (pintype "passive"))
      (node (ref "X1") (pin "3") (pinfunction "KL_3") (pintype "passive"))
    )
    (net (code "53") (name "/PHC") (class "Default")
      (node (ref "L3") (pin "1") (pinfunction "1_1") (pintype "passive"))
      (node (ref "X1") (pin "2") (pinfunction "KL_2") (pintype "passive"))
    )
    (net (code "54") (name "/PM1_ADE") (class "Default")
      (node (ref "R59") (pin "2") (pinfunction "2_2") (pintype "passive"))
      (node (ref "U1") (pin "5") (pinfunction "PM1_5") (pintype "passive"))
      (node (ref "X4") (pin "12") (pinfunction "IO27/A2_7_12") (pintype "bidirectional"))
    )
    (net (code "55") (name "/REF") (class "Default")
      (node (ref "C41") (pin "2") (pinfunction "2_2") (pintype "passive"))
      (node (ref "C45") (pin "2") (pinfunction "2_2") (pintype "passive"))
      (node (ref "U1") (pin "16") (pinfunction "REF_16") (pintype "passive"))
    )
    (net (code "56") (name "/RESET") (class "Default")
      (node (ref "C18") (pin "1") (pinfunction "1_1") (pintype "passive"))
      (node (ref "R1") (pin "1") (pinfunction "1_1") (pintype "passive"))
      (node (ref "SV2") (pin "6") (pinfunction "6_6") (pintype "passive"))
      (node (ref "SW2") (pin "B") (pinfunction "S_B") (pintype "passive"))
      (node (ref "SW2") (pin "B'") (pinfunction "S1_B'") (pintype "passive"))
      (node (ref "X4") (pin "3") (pinfunction "EN_3") (pintype "input"))
    )
    (net (code "57") (name "/RESET_ADE") (class "Default")
      (node (ref "C1") (pin "1") (pinfunction "1_1") (pintype "passive"))
      (node (ref "R2") (pin "1") (pinfunction "1_1") (pintype "passive"))
      (node (ref "U1") (pin "6") (pinfunction "RESET*_6") (pintype "passive"))
      (node (ref "X4") (pin "11") (pinfunction "IO26/DAC2/A2_9_11") (pintype "bidirectional"))
    )
    (net (code "58") (name "/RX0") (class "Default")
      (node (ref "SV2") (pin "4") (pinfunction "4_4") (pintype "passive"))
      (node (ref "X4") (pin "34") (pinfunction "RXD0_34") (pintype "input"))
    )
    (net (code "59") (name "/SCL") (class "Default")
      (node (ref "R32") (pin "2") (pinfunction "2_2") (pintype "passive"))
      (node (ref "SV1") (pin "5") (pinfunction "5_5") (pintype "passive"))
      (node (ref "U2") (pin "8") (pinfunction "SCL_8") (pintype "bidirectional"))
      (node (ref "X4") (pin "36") (pinfunction "IO22_36") (pintype "bidirectional"))
    )
    (net (code "60") (name "/SCLK_ADE") (class "Default")
      (node (ref "R45") (pin "1") (pinfunction "1_1") (pintype "passive"))
      (node (ref "U1") (pin "37") (pinfunction "SCLK_37") (pintype "passive"))
      (node (ref "USD") (pin "5") (pinfunction "SCLK_5") (pintype "bidirectional"))
      (node (ref "X4") (pin "30") (pinfunction "IO18_30") (pintype "bidirectional"))
    )
    (net (code "61") (name "/SDA") (class "Default")
      (node (ref "R34") (pin "2") (pinfunction "2_2") (pintype "passive"))
      (node (ref "SV1") (pin "4") (pinfunction "4_4") (pintype "passive"))
      (node (ref "U2") (pin "1") (pinfunction "SDA_1") (pintype "bidirectional"))
      (node (ref "X4") (pin "33") (pinfunction "IO21_33") (pintype "bidirectional"))
    )
    (net (code "62") (name "/SS_ADE") (class "Default")
      (node (ref "R57") (pin "1") (pinfunction "1_1") (pintype "passive"))
      (node (ref "U1") (pin "40") (pinfunction "SS*_40") (pintype "passive"))
      (node (ref "X4") (pin "13") (pinfunction "IO14/A2_6_13") (pintype "bidirectional"))
    )
    (net (code "63") (name "/TX0") (class "Default")
      (node (ref "SV2") (pin "5") (pinfunction "5_5") (pintype "passive"))
      (node (ref "X4") (pin "35") (pinfunction "TXD0_35") (pintype "output"))
    )
    (net (code "64") (name "/VAN") (class "Default")
      (node (ref "C27") (pin "1") (pinfunction "1_1") (pintype "passive"))
      (node (ref "C52") (pin "1") (pinfunction "1_1") (pintype "passive"))
      (node (ref "R33") (pin "1") (pinfunction "1_1") (pintype "passive"))
      (node (ref "U1") (pin "19") (pinfunction "VAN_19") (pintype "passive"))
    )
    (net (code "65") (name "/VAP") (class "Default")
      (node (ref "C23") (pin "1") (pinfunction "1_1") (pintype "passive"))
      (node (ref "C52") (pin "2") (pinfunction "2_2") (pintype "passive"))
      (node (ref "R18") (pin "2") (pinfunction "2_2") (pintype "passive"))
      (node (ref "R29") (pin "2") (pinfunction "2_2") (pintype "passive"))
      (node (ref "U1") (pin "20") (pinfunction "VAP_20") (pintype "passive"))
    )
    (net (code "66") (name "/VBN") (class "Default")
      (node (ref "C35") (pin "1") (pinfunction "1_1") (pintype "passive"))
      (node (ref "C54") (pin "1") (pinfunction "1_1") (pintype "passive"))
      (node (ref "R43") (pin "1") (pinfunction "1_1") (pintype "passive"))
      (node (ref "U1") (pin "21") (pinfunction "VBN_21") (pintype "passive"))
    )
    (net (code "67") (name "/VBP") (class "Default")
      (node (ref "C33") (pin "1") (pinfunction "1_1") (pintype "passive"))
      (node (ref "C54") (pin "2") (pinfunction "2_2") (pintype "passive"))
      (node (ref "R31") (pin "2") (pinfunction "2_2") (pintype "passive"))
      (node (ref "R37") (pin "2") (pinfunction "2_2") (pintype "passive"))
      (node (ref "U1") (pin "22") (pinfunction "VBP_22") (pintype "passive"))
    )
    (net (code "68") (name "/VCN") (class "Default")
      (node (ref "C36") (pin "1") (pinfunction "1_1") (pintype "passive"))
      (node (ref "C55") (pin "1") (pinfunction "1_1") (pintype "passive"))
      (node (ref "R44") (pin "1") (pinfunction "1_1") (pintype "passive"))
      (node (ref "U1") (pin "23") (pinfunction "VCN_23") (pintype "passive"))
    )
    (net (code "69") (name "/VCP") (class "Default")
      (node (ref "C34") (pin "1") (pinfunction "1_1") (pintype "passive"))
      (node (ref "C55") (pin "2") (pinfunction "2_2") (pintype "passive"))
      (node (ref "R39") (pin "2") (pinfunction "2_2") (pintype "passive"))
      (node (ref "R42") (pin "2") (pinfunction "2_2") (pintype "passive"))
      (node (ref "U1") (pin "24") (pinfunction "VCP_24") (pintype "passive"))
    )
    (net (code "70") (name "/~{EVI}") (class "Default")
      (node (ref "R27") (pin "1") (pinfunction "1_1") (pintype "passive"))
      (node (ref "U2") (pin "7") (pinfunction "EVI_7") (pintype "bidirectional"))
    )
    (net (code "71") (name "/~{INT}") (class "Default")
      (node (ref "R28") (pin "1") (pinfunction "1_1") (pintype "passive"))
      (node (ref "U2") (pin "6") (pinfunction "~{INT}_6") (pintype "bidirectional"))
    )
    (net (code "72") (name "GND") (class "Default")
      (node (ref "BT2") (pin "GND") (pinfunction "-_GND") (pintype "power_in"))
      (node (ref "C10") (pin "2") (pinfunction "2_2") (pintype "passive"))
      (node (ref "C11") (pin "1") (pinfunction "1_1") (pintype "passive"))
      (node (ref "C12") (pin "2") (pinfunction "2_2") (pintype "passive"))
      (node (ref "C13") (pin "1") (pinfunction "1_1") (pintype "passive"))
      (node (ref "C14") (pin "2") (pinfunction "2_2") (pintype "passive"))
      (node (ref "C15") (pin "2") (pinfunction "2_2") (pintype "passive"))
      (node (ref "C16") (pin "1") (pinfunction "1_1") (pintype "passive"))
      (node (ref "C17") (pin "2") (pinfunction "2_2") (pintype "passive"))
      (node (ref "C18") (pin "2") (pinfunction "2_2") (pintype "passive"))
      (node (ref "C19") (pin "1") (pinfunction "1_1") (pintype "passive"))
      (node (ref "C2") (pin "2") (pinfunction "2_2") (pintype "passive"))
      (node (ref "C21") (pin "1") (pinfunction "1_1") (pintype "passive"))
      (node (ref "C23") (pin "2") (pinfunction "2_2") (pintype "passive"))
      (node (ref "C27") (pin "2") (pinfunction "2_2") (pintype "passive"))
      (node (ref "C29") (pin "2") (pinfunction "2_2") (pintype "passive"))
      (node (ref "C3") (pin "1") (pinfunction "1_1") (pintype "passive"))
      (node (ref "C30") (pin "1") (pinfunction "1_1") (pintype "passive"))
      (node (ref "C33") (pin "2") (pinfunction "2_2") (pintype "passive"))
      (node (ref "C34") (pin "2") (pinfunction "2_2") (pintype "passive"))
      (node (ref "C35") (pin "2") (pinfunction "2_2") (pintype "passive"))
      (node (ref "C36") (pin "2") (pinfunction "2_2") (pintype "passive"))
      (node (ref "C37") (pin "2") (pinfunction "2_2") (pintype "passive"))
      (node (ref "C38") (pin "2") (pinfunction "2_2") (pintype "passive"))
      (node (ref "C4") (pin "2") (pinfunction "2_2") (pintype "passive"))
      (node (ref "C40") (pin "1") (pinfunction "1_1") (pintype "passive"))
      (node (ref "C41") (pin "1") (pinfunction "1_1") (pintype "passive"))
      (node (ref "C42") (pin "2") (pinfunction "2_2") (pintype "passive"))
      (node (ref "C43") (pin "2") (pinfunction "2_2") (pintype "passive"))
      (node (ref "C44") (pin "-") (pinfunction "-_-") (pintype "passive"))
      (node (ref "C45") (pin "1") (pinfunction "1_1") (pintype "passive"))
      (node (ref "C46") (pin "1") (pinfunction "1_1") (pintype "passive"))
      (node (ref "C47") (pin "1") (pinfunction "1_1") (pintype "passive"))
      (node (ref "C5") (pin "1") (pinfunction "1_1") (pintype "passive"))
      (node (ref "C6") (pin "2") (pinfunction "2_2") (pintype "passive"))
      (node (ref "C7") (pin "1") (pinfunction "1_1") (pintype "passive"))
      (node (ref "C8") (pin "2") (pinfunction "2_2") (pintype "passive"))
      (node (ref "C9") (pin "1") (pinfunction "1_1") (pintype "passive"))
      (node (ref "CF3") (pin "C") (pinfunction "C_C") (pintype "passive"))
      (node (ref "CF4") (pin "C") (pinfunction "C_C") (pintype "passive"))
      (node (ref "CT1") (pin "2") (pinfunction "KL_2") (pintype "passive"))
      (node (ref "HLK1") (pin "P$3") (pinfunction "-VO_P$3") (pintype "bidirectional"))
      (node (ref "IC2") (pin "1") (pinfunction "GND_1") (pintype "power_in"))
      (node (ref "L4") (pin "2") (pinfunction "2_2") (pintype "passive"))
      (node (ref "ON/OFF") (pin "C") (pinfunction "C_C") (pintype "passive"))
      (node (ref "Q1") (pin "3") (pinfunction "3_3") (pintype "passive"))
      (node (ref "Q2") (pin "3") (pinfunction "3_3") (pintype "passive"))
      (node (ref "Q3") (pin "3") (pinfunction "3_3") (pintype "passive"))
      (node (ref "Q4") (pin "3") (pinfunction "3_3") (pintype "passive"))
      (node (ref "Q5") (pin "3") (pinfunction "3_3") (pintype "passive"))
      (node (ref "Q6") (pin "3") (pinfunction "3_3") (pintype "passive"))
      (node (ref "Q7") (pin "3") (pinfunction "3_3") (pintype "passive"))
      (node (ref "Q8") (pin "3") (pinfunction "3_3") (pintype "passive"))
      (node (ref "Q9") (pin "2") (pinfunction "2_2") (pintype "passive"))
      (node (ref "Q9") (pin "4") (pinfunction "4_4") (pintype "passive"))
      (node (ref "R11") (pin "2") (pinfunction "2_2") (pintype "passive"))
      (node (ref "R12") (pin "1") (pinfunction "1_1") (pintype "passive"))
      (node (ref "R19") (pin "2") (pinfunction "2_2") (pintype "passive"))
      (node (ref "R20") (pin "1") (pinfunction "1_1") (pintype "passive"))
      (node (ref "R29") (pin "1") (pinfunction "1_1") (pintype "passive"))
      (node (ref "R3") (pin "2") (pinfunction "2_2") (pintype "passive"))
      (node (ref "R33") (pin "2") (pinfunction "2_2") (pintype "passive"))
      (node (ref "R37") (pin "1") (pinfunction "1_1") (pintype "passive"))
      (node (ref "R4") (pin "1") (pinfunction "1_1") (pintype "passive"))
      (node (ref "R40") (pin "1") (pinfunction "1_1") (pintype "passive"))
      (node (ref "R42") (pin "1") (pinfunction "1_1") (pintype "passive"))
      (node (ref "R43") (pin "2") (pinfunction "2_2") (pintype "passive"))
      (node (ref "R44") (pin "2") (pinfunction "2_2") (pintype "passive"))
      (node (ref "R5") (pin "2") (pinfunction "2_2") (pintype "passive"))
      (node (ref "R59") (pin "1") (pinfunction "1_1") (pintype "passive"))
      (node (ref "R6") (pin "1") (pinfunction "1_1") (pintype "passive"))
      (node (ref "SV1") (pin "2") (pinfunction "2_2") (pintype "passive"))
      (node (ref "SV2") (pin "1") (pinfunction "1_1") (pintype "passive"))
      (node (ref "SW2") (pin "A") (pinfunction "P_A") (pintype "passive"))
      (node (ref "SW2") (pin "A'") (pinfunction "P1_A'") (pintype "passive"))
      (node (ref "U1") (pin "15") (pinfunction "REFGND_15") (pintype "passive"))
      (node (ref "U1") (pin "2") (pinfunction "DGND_2") (pintype "passive"))
      (node (ref "U1") (pin "26") (pinfunction "AGND_26") (pintype "passive"))
      (node (ref "U1") (pin "28") (pinfunction "GND_28") (pintype "passive"))
      (node (ref "U1") (pin "41") (pinfunction "EP(GND)_41") (pintype "passive"))
      (node (ref "U2") (pin "5") (pinfunction "GND_5") (pintype "bidirectional"))
      (node (ref "USD") (pin "6") (pinfunction "VSS_6") (pintype "bidirectional"))
      (node (ref "X4") (pin "1") (pinfunction "GND_1") (pintype "passive"))
      (node (ref "X4") (pin "15") (pinfunction "GND_15") (pintype "passive"))
      (node (ref "X4") (pin "38") (pinfunction "GND_38") (pintype "passive"))
      (node (ref "X4") (pin "P$1") (pinfunction "GND_P$1") (pintype "passive"))
    )
    (net (code "73") (name "Net-(C2-Pad1)") (class "Default")
      (node (ref "C2") (pin "1") (pinfunction "1_1") (pintype "passive"))
      (node (ref "R7") (pin "2") (pinfunction "2_2") (pintype "passive"))
      (node (ref "R9") (pin "1") (pinfunction "1_1") (pintype "passive"))
    )
    (net (code "74") (name "Net-(C3-Pad2)") (class "Default")
      (node (ref "C3") (pin "2") (pinfunction "2_2") (pintype "passive"))
      (node (ref "R10") (pin "1") (pinfunction "1_1") (pintype "passive"))
      (node (ref "R8") (pin "1") (pinfunction "1_1") (pintype "passive"))
    )
    (net (code "75") (name "Net-(C6-Pad1)") (class "Default")
      (node (ref "C6") (pin "1") (pinfunction "1_1") (pintype "passive"))
      (node (ref "R14") (pin "2") (pinfunction "2_2") (pintype "passive"))
      (node (ref "R16") (pin "1") (pinfunction "1_1") (pintype "passive"))
    )
    (net (code "76") (name "Net-(C7-Pad2)") (class "Default")
      (node (ref "C7") (pin "2") (pinfunction "2_2") (pintype "passive"))
      (node (ref "R15") (pin "1") (pinfunction "1_1") (pintype "passive"))
      (node (ref "R17") (pin "1") (pinfunction "1_1") (pintype "passive"))
    )
    (net (code "77") (name "Net-(C10-Pad1)") (class "Default")
      (node (ref "C10") (pin "1") (pinfunction "1_1") (pintype "passive"))
      (node (ref "R23") (pin "2") (pinfunction "2_2") (pintype "passive"))
      (node (ref "R25") (pin "1") (pinfunction "1_1") (pintype "passive"))
    )
    (net (code "78") (name "Net-(C11-Pad2)") (class "Default")
      (node (ref "C11") (pin "2") (pinfunction "2_2") (pintype "passive"))
      (node (ref "R24") (pin "1") (pinfunction "1_1") (pintype "passive"))
      (node (ref "R26") (pin "1") (pinfunction "1_1") (pintype "passive"))
    )
    (net (code "79") (name "Net-(C15-Pad1)") (class "Default")
      (node (ref "C15") (pin "1") (pinfunction "1_1") (pintype "passive"))
      (node (ref "R21") (pin "2") (pinfunction "2_2") (pintype "passive"))
      (node (ref "R35") (pin "1") (pinfunction "1_1") (pintype "passive"))
    )
    (net (code "80") (name "Net-(C16-Pad2)") (class "Default")
      (node (ref "C16") (pin "2") (pinfunction "2_2") (pintype "passive"))
      (node (ref "R22") (pin "1") (pinfunction "1_1") (pintype "passive"))
      (node (ref "R36") (pin "1") (pinfunction "1_1") (pintype "passive"))
    )
    (net (code "81") (name "Net-(CF3-PadA)") (class "Default")
      (node (ref "CF3") (pin "A") (pinfunction "A_A") (pintype "passive"))
      (node (ref "R56") (pin "1") (pinfunction "1_1") (pintype "passive"))
    )
    (net (code "82") (name "Net-(CF4-PadA)") (class "Default")
      (node (ref "CF4") (pin "A") (pinfunction "A_A") (pintype "passive"))
      (node (ref "R53") (pin "1") (pinfunction "1_1") (pintype "passive"))
    )
    (net (code "83") (name "Net-(D1-C)") (class "Default")
      (node (ref "C19") (pin "2") (pinfunction "2_2") (pintype "passive"))
      (node (ref "D1") (pin "3") (pinfunction "C_3") (pintype "passive"))
      (node (ref "U2") (pin "3") (pinfunction "VDD_3") (pintype "bidirectional"))
    )
    (net (code "84") (name "Net-(HLK1-AC1)") (class "Default")
      (node (ref "HLK1") (pin "P$1") (pinfunction "AC1_P$1") (pintype "bidirectional"))
      (node (ref "JPHA") (pin "2") (pinfunction "2_2") (pintype "passive"))
    )
    (net (code "85") (name "Net-(IRQ0-PadA)") (class "Default")
      (node (ref "IRQ0") (pin "A") (pinfunction "A_A") (pintype "passive"))
      (node (ref "R54") (pin "1") (pinfunction "1_1") (pintype "passive"))
    )
    (net (code "86") (name "Net-(IRQ1-PadA)") (class "Default")
      (node (ref "IRQ1") (pin "A") (pinfunction "A_A") (pintype "passive"))
      (node (ref "R55") (pin "1") (pinfunction "1_1") (pintype "passive"))
    )
    (net (code "87") (name "Net-(L1-Pad2)") (class "Default")
      (node (ref "L1") (pin "2") (pinfunction "2_2") (pintype "passive"))
      (node (ref "R47") (pin "1") (pinfunction "1_1") (pintype "passive"))
    )
    (net (code "88") (name "Net-(L2-Pad2)") (class "Default")
      (node (ref "L2") (pin "2") (pinfunction "2_2") (pintype "passive"))
      (node (ref "R49") (pin "1") (pinfunction "1_1") (pintype "passive"))
    )
    (net (code "89") (name "Net-(L3-Pad2)") (class "Default")
      (node (ref "L3") (pin "2") (pinfunction "2_2") (pintype "passive"))
      (node (ref "R50") (pin "1") (pinfunction "1_1") (pintype "passive"))
    )
    (net (code "90") (name "Net-(ON/OFF-PadA)") (class "Default")
      (node (ref "ON/OFF") (pin "A") (pinfunction "A_A") (pintype "passive"))
      (node (ref "R58") (pin "1") (pinfunction "1_1") (pintype "passive"))
    )
    (net (code "91") (name "Net-(R13-Pad1)") (class "Default")
      (node (ref "R13") (pin "1") (pinfunction "1_1") (pintype "passive"))
      (node (ref "R47") (pin "2") (pinfunction "2_2") (pintype "passive"))
    )
    (net (code "92") (name "Net-(R13-Pad2)") (class "Default")
      (node (ref "R13") (pin "2") (pinfunction "2_2") (pintype "passive"))
      (node (ref "R18") (pin "1") (pinfunction "1_1") (pintype "passive"))
    )
    (net (code "93") (name "Net-(R30-Pad1)") (class "Default")
      (node (ref "R30") (pin "1") (pinfunction "1_1") (pintype "passive"))
      (node (ref "R49") (pin "2") (pinfunction "2_2") (pintype "passive"))
    )
    (net (code "94") (name "Net-(R30-Pad2)") (class "Default")
      (node (ref "R30") (pin "2") (pinfunction "2_2") (pintype "passive"))
      (node (ref "R31") (pin "1") (pinfunction "1_1") (pintype "passive"))
    )
    (net (code "95") (name "Net-(R38-Pad1)") (class "Default")
      (node (ref "R38") (pin "1") (pinfunction "1_1") (pintype "passive"))
      (node (ref "R50") (pin "2") (pinfunction "2_2") (pintype "passive"))
    )
    (net (code "96") (name "Net-(R38-Pad2)") (class "Default")
      (node (ref "R38") (pin "2") (pinfunction "2_2") (pintype "passive"))
      (node (ref "R39") (pin "1") (pinfunction "1_1") (pintype "passive"))
    )
    (net (code "97") (name "unconnected-(U2-CLKOUT-Pad2)") (class "Default")
      (node (ref "U2") (pin "2") (pinfunction "CLKOUT_2") (pintype "bidirectional"))
    )
    (net (code "98") (name "unconnected-(X4-CLK-Pad20)") (class "Default")
      (node (ref "X4") (pin "20") (pinfunction "CLK_20") (pintype "bidirectional"))
    )
    (net (code "99") (name "unconnected-(X4-CMD-Pad19)") (class "Default")
      (node (ref "X4") (pin "19") (pinfunction "CMD_19") (pintype "bidirectional"))
    )
    (net (code "100") (name "unconnected-(X4-SD0-Pad21)") (class "Default")
      (node (ref "X4") (pin "21") (pinfunction "SD0_21") (pintype "bidirectional"))
    )
    (net (code "101") (name "unconnected-(X4-SD1-Pad22)") (class "Default")
      (node (ref "X4") (pin "22") (pinfunction "SD1_22") (pintype "bidirectional"))
    )
    (net (code "102") (name "unconnected-(X4-SD2-Pad17)") (class "Default")
      (node (ref "X4") (pin "17") (pinfunction "SD2_17") (pintype "bidirectional"))
    )
    (net (code "103") (name "unconnected-(X4-SD3-Pad18)") (class "Default")
      (node (ref "X4") (pin "18") (pinfunction "SD3_18") (pintype "bidirectional"))
    )
  )
)
